# DM1098OAKW_USB.net
KiCad netlist of a schematic drawn in Altium Designer
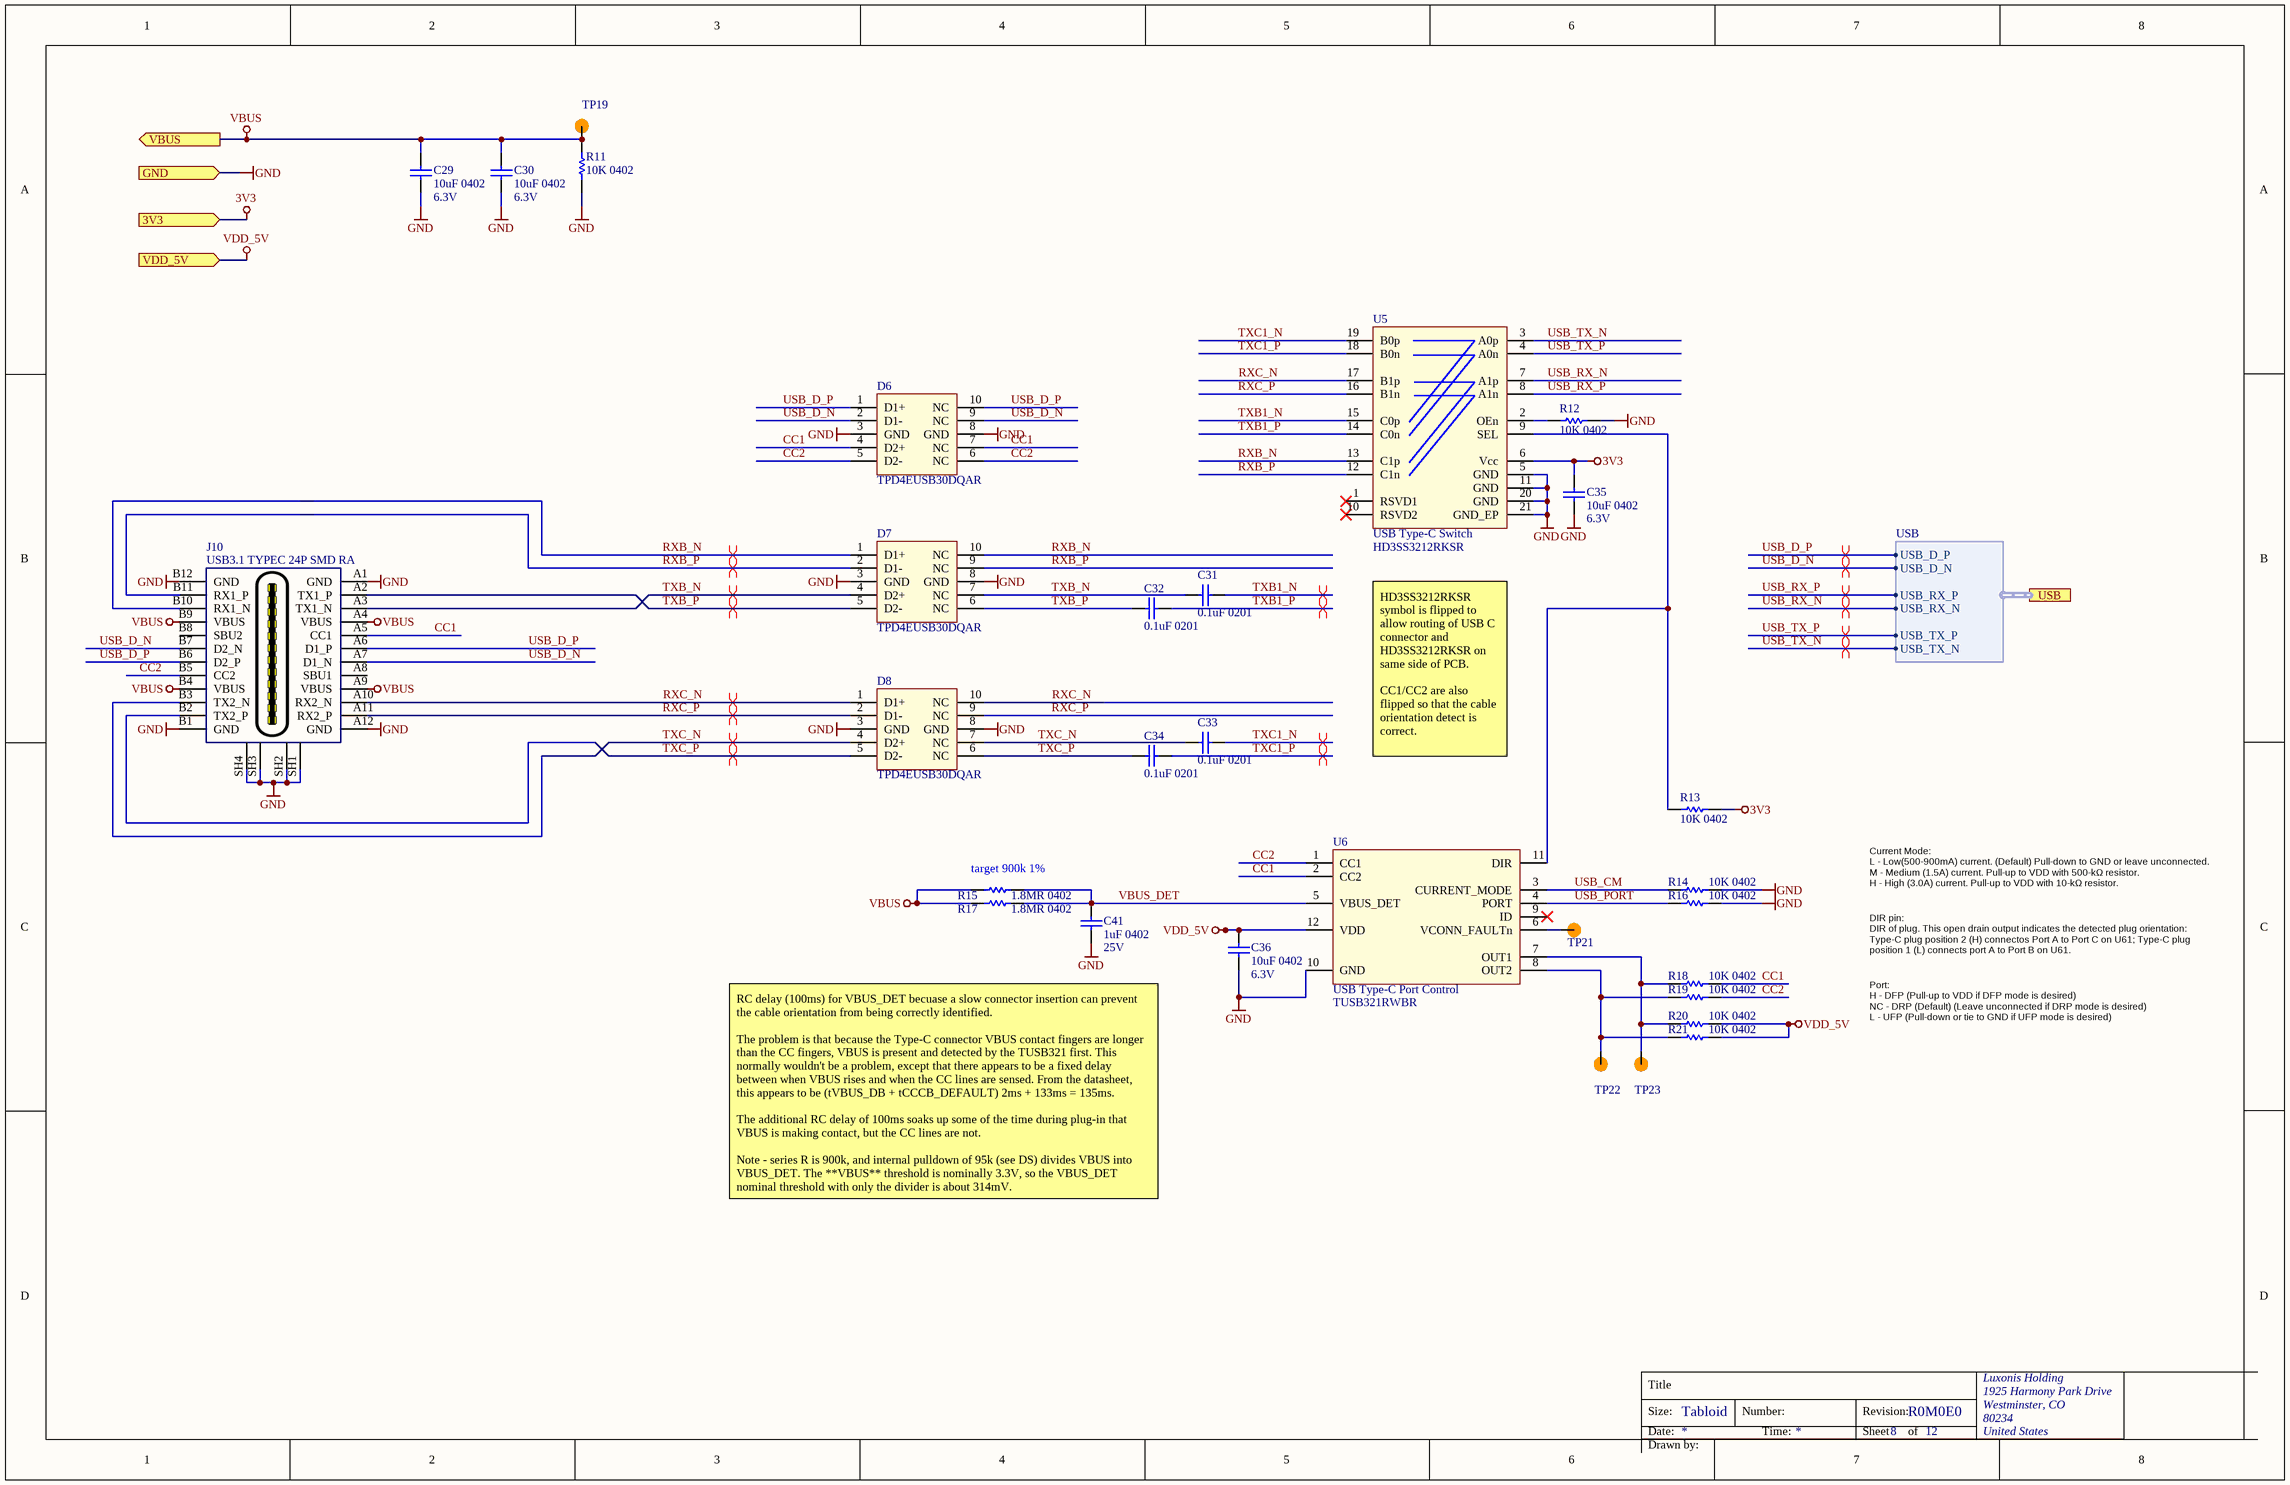
[diagram p0: DM1098OAKW_USB.SchDoc]

(export (version "E")
  (design (tool "Eeschema 10.0.6"))
  (components
    (comp (ref "C29")
      (value "10uF 0402")
      (footprint "CAP_Altium_Vault_Generic:CAPC0402(1005)70_L")
      (description "CAP CER 10UF 6.3V X5R 0402 20%")
      (fields (field (name "TOLERANCE") "20%") (field (name "VOLTAGE RATING") "6.3V"))
      (libsource (lib "LuxonisMaster") (part "GRM155R60J106ME15D"))
    )
    (comp (ref "C30")
      (value "10uF 0402")
      (footprint "CAP_Altium_Vault_Generic:CAPC0402(1005)70_L")
      (description "CAP CER 10UF 6.3V X5R 0402 20%")
      (fields (field (name "TOLERANCE") "20%") (field (name "VOLTAGE RATING") "6.3V"))
      (libsource (lib "LuxonisMaster") (part "GRM155R60J106ME15D"))
    )
    (comp (ref "C31")
      (value "0.1uF 0201")
      (footprint "CAP_Altium_Vault_Generic:CAPC0201(0603)33_L")
      (description "CAP CER 0.1UF 10V X5R 0201")
      (fields (field (name "TOLERANCE") "10%") (field (name "VOLTAGE") "10V"))
      (libsource (lib "LuxonisMaster") (part "GRM033R61A104KE15D"))
    )
    (comp (ref "C32")
      (value "0.1uF 0201")
      (footprint "CAP_Altium_Vault_Generic:CAPC0201(0603)33_L")
      (description "CAP CER 0.1UF 10V X5R 0201")
      (fields (field (name "TOLERANCE") "10%") (field (name "VOLTAGE") "10V"))
      (libsource (lib "LuxonisMaster") (part "GRM033R61A104KE15D"))
    )
    (comp (ref "C33")
      (value "0.1uF 0201")
      (footprint "CAP_Altium_Vault_Generic:CAPC0201(0603)33_L")
      (description "CAP CER 0.1UF 10V X5R 0201")
      (fields (field (name "TOLERANCE") "10%") (field (name "VOLTAGE") "10V"))
      (libsource (lib "LuxonisMaster") (part "GRM033R61A104KE15D"))
    )
    (comp (ref "C34")
      (value "0.1uF 0201")
      (footprint "CAP_Altium_Vault_Generic:CAPC0201(0603)33_L")
      (description "CAP CER 0.1UF 10V X5R 0201")
      (fields (field (name "TOLERANCE") "10%") (field (name "VOLTAGE") "10V"))
      (libsource (lib "LuxonisMaster") (part "GRM033R61A104KE15D"))
    )
    (comp (ref "C35")
      (value "10uF 0402")
      (footprint "CAP_Altium_Vault_Generic:CAPC0402(1005)70_L")
      (description "CAP CER 10UF 6.3V X5R 0402 20%")
      (fields (field (name "TOLERANCE") "20%") (field (name "VOLTAGE RATING") "6.3V"))
      (libsource (lib "LuxonisMaster") (part "GRM155R60J106ME15D"))
    )
    (comp (ref "C36")
      (value "10uF 0402")
      (footprint "CAP_Altium_Vault_Generic:CAPC0402(1005)70_L")
      (description "CAP CER 10UF 6.3V X5R 0402 20%")
      (fields (field (name "TOLERANCE") "20%") (field (name "VOLTAGE RATING") "6.3V"))
      (libsource (lib "LuxonisMaster") (part "GRM155R60J106ME15D"))
    )
    (comp (ref "C41")
      (value "1uF 0402")
      (footprint "CAP_Altium_Vault_Generic:CAPC0402(1005)70_N")
      (description "CAP CER 1UF 25V X5R 0402 10%")
      (fields
        (field (name "TOLERANCE") "10%")
        (field (name "VOLTAGE") "25V")
        (field (name "VOLTAGE RATING") "25V")
      )
      (libsource (lib "LuxonisMaster") (part "GRM155R61E105KA12D"))
    )
    (comp (ref "D6")
      (value "TPD4EUSB30DQAR")
      (footprint "LuxonisMaster:TPD4EUSB30DQAR")
      (description "TVS DIODE 5.5V 8V 10SON 8V Clamp 1A (8/20µs) Ipp Tvs Diode Surface Mount 10-USON (2.5x1)")
      (libsource (lib "LuxonisMaster") (part "TPD4EUSB30DQAR"))
    )
    (comp (ref "D7")
      (value "TPD4EUSB30DQAR")
      (footprint "LuxonisMaster:TPD4EUSB30DQAR")
      (description "TVS DIODE 5.5V 8V 10SON 8V Clamp 1A (8/20µs) Ipp Tvs Diode Surface Mount 10-USON (2.5x1)")
      (libsource (lib "LuxonisMaster") (part "TPD4EUSB30DQAR"))
    )
    (comp (ref "D8")
      (value "TPD4EUSB30DQAR")
      (footprint "LuxonisMaster:TPD4EUSB30DQAR")
      (description "TVS DIODE 5.5V 8V 10SON 8V Clamp 1A (8/20µs) Ipp Tvs Diode Surface Mount 10-USON (2.5x1)")
      (libsource (lib "LuxonisMaster") (part "TPD4EUSB30DQAR"))
    )
    (comp (ref "J10")
      (value "USB3.1 TYPEC 24P SMD RA")
      (footprint "LuxonisMaster:105450-0101")
      (description "CONN RCP USB3.1 TYPEC 24P SMD RA")
      (libsource (lib "LuxonisMaster") (part "105450-0101"))
    )
    (comp (ref "R11")
      (value "10K 0402")
      (footprint "RES_Altium_Vault_Generic:RESC0402(1005)_L")
      (fields (field (name "TOLERANCE") "1%"))
      (libsource (lib "LuxonisMaster") (part "RC0402FR-1310KL"))
    )
    (comp (ref "R12")
      (value "10K 0402")
      (footprint "RES_Altium_Vault_Generic:RESC0402(1005)_L")
      (fields (field (name "TOLERANCE") "1%"))
      (libsource (lib "LuxonisMaster") (part "RC0402FR-1310KL"))
    )
    (comp (ref "R13")
      (value "10K 0402")
      (footprint "RES_Altium_Vault_Generic:RESC0402(1005)_L")
      (fields (field (name "TOLERANCE") "1%"))
      (libsource (lib "LuxonisMaster") (part "RC0402FR-1310KL"))
    )
    (comp (ref "R14")
      (value "10K 0402")
      (footprint "RES_Altium_Vault_Generic:RESC0402(1005)_L")
      (fields (field (name "TOLERANCE") "1%"))
      (libsource (lib "LuxonisMaster") (part "RC0402FR-1310KL"))
    )
    (comp (ref "R15")
      (value "1.8MR 0402")
      (footprint "RES_Altium_Vault_Generic:RESC0402(1005)_L")
      (description "RES SMD 1.8M OHM 1% 1/16W 0402")
      (fields (field (name "TOLERANCE") "1%"))
      (libsource (lib "LuxonisMaster") (part "CRCW04021M80FKED"))
    )
    (comp (ref "R16")
      (value "10K 0402")
      (footprint "RES_Altium_Vault_Generic:RESC0402(1005)_L")
      (fields (field (name "TOLERANCE") "1%"))
      (libsource (lib "LuxonisMaster") (part "RC0402FR-1310KL"))
    )
    (comp (ref "R17")
      (value "1.8MR 0402")
      (footprint "RES_Altium_Vault_Generic:RESC0402(1005)_L")
      (description "RES SMD 1.8M OHM 1% 1/16W 0402")
      (fields (field (name "TOLERANCE") "1%"))
      (libsource (lib "LuxonisMaster") (part "CRCW04021M80FKED"))
    )
    (comp (ref "R18")
      (value "10K 0402")
      (footprint "RES_Altium_Vault_Generic:RESC0402(1005)_L")
      (fields (field (name "TOLERANCE") "1%"))
      (libsource (lib "LuxonisMaster") (part "RC0402FR-1310KL"))
    )
    (comp (ref "R19")
      (value "10K 0402")
      (footprint "RES_Altium_Vault_Generic:RESC0402(1005)_L")
      (fields (field (name "TOLERANCE") "1%"))
      (libsource (lib "LuxonisMaster") (part "RC0402FR-1310KL"))
    )
    (comp (ref "R20")
      (value "10K 0402")
      (footprint "RES_Altium_Vault_Generic:RESC0402(1005)_L")
      (fields (field (name "TOLERANCE") "1%"))
      (libsource (lib "LuxonisMaster") (part "RC0402FR-1310KL"))
    )
    (comp (ref "R21")
      (value "10K 0402")
      (footprint "RES_Altium_Vault_Generic:RESC0402(1005)_L")
      (fields (field (name "TOLERANCE") "1%"))
      (libsource (lib "LuxonisMaster") (part "RC0402FR-1310KL"))
    )
    (comp (ref "TP19")
      (value "TP100_200_NS")
      (footprint "LuxonisMaster:TP100_200_NS")
      (libsource (lib "LuxonisMaster") (part "TEST_POINT"))
    )
    (comp (ref "TP21")
      (value "TP075_150_NS")
      (footprint "LuxonisMaster:TP075_150_NS")
      (libsource (lib "LuxonisMaster") (part "TEST_POINT"))
    )
    (comp (ref "TP22")
      (value "TP075_150_NS")
      (footprint "LuxonisMaster:TP075_150_NS")
      (libsource (lib "LuxonisMaster") (part "TEST_POINT"))
    )
    (comp (ref "TP23")
      (value "TP075_150_NS")
      (footprint "LuxonisMaster:TP075_150_NS")
      (libsource (lib "LuxonisMaster") (part "TEST_POINT"))
    )
    (comp (ref "U5")
      (value "USB Type-C Switch")
      (footprint "LuxonisMaster:HD3SS3212RKSR")
      (description "IC MUX 2:1 8 OHM 20VQFN")
      (fields (field (name "MANUFACTURER PART NUMBER 1") "HD3SS3212RKSR"))
      (libsource (lib "LuxonisMaster") (part "HD3SS3212RKSR"))
    )
    (comp (ref "U6")
      (value "USB Type-C Port Control")
      (footprint "LuxonisMaster:TUSB321RWBR")
      (description "IC USB PORT CONTROL TYPE-C 12X2Q")
      (fields (field (name "MANUFACTURER PART NUMBER 1") "TUSB321RWBR"))
      (libsource (lib "LuxonisMaster") (part "TUSB321RWBR"))
    )
  )
  (nets
    (net (code "2") (name "/CC1") (class "Default")
      (node (ref "D6") (pin "4") (pinfunction "D2+_4") (pintype "passive"))
      (node (ref "D6") (pin "7") (pinfunction "NC_7") (pintype "passive"))
      (node (ref "J10") (pin "A5") (pinfunction "CC1_A5") (pintype "passive"))
      (node (ref "R18") (pin "2") (pinfunction "2_2") (pintype "passive"))
      (node (ref "U6") (pin "2") (pinfunction "CC2_2") (pintype "passive"))
    )
    (net (code "3") (name "/CC2") (class "Default")
      (node (ref "D6") (pin "5") (pinfunction "D2-_5") (pintype "passive"))
      (node (ref "D6") (pin "6") (pinfunction "NC_6") (pintype "passive"))
      (node (ref "J10") (pin "B5") (pinfunction "CC2_B5") (pintype "passive"))
      (node (ref "R19") (pin "2") (pinfunction "2_2") (pintype "passive"))
      (node (ref "U6") (pin "1") (pinfunction "CC1_1") (pintype "passive"))
    )
    (net (code "4") (name "/RXB_N") (class "Default")
      (node (ref "D7") (pin "1") (pinfunction "D1+_1") (pintype "passive"))
      (node (ref "D7") (pin "10") (pinfunction "NC_10") (pintype "passive"))
      (node (ref "J10") (pin "B10") (pinfunction "RX1_N_B10") (pintype "passive"))
      (node (ref "U5") (pin "13") (pinfunction "C1p_13") (pintype "passive"))
    )
    (net (code "5") (name "/RXB_P") (class "Default")
      (node (ref "D7") (pin "2") (pinfunction "D1-_2") (pintype "passive"))
      (node (ref "D7") (pin "9") (pinfunction "NC_9") (pintype "passive"))
      (node (ref "J10") (pin "B11") (pinfunction "RX1_P_B11") (pintype "passive"))
      (node (ref "U5") (pin "12") (pinfunction "C1n_12") (pintype "passive"))
    )
    (net (code "6") (name "/RXC_N") (class "Default")
      (node (ref "D8") (pin "1") (pinfunction "D1+_1") (pintype "passive"))
      (node (ref "D8") (pin "10") (pinfunction "NC_10") (pintype "passive"))
      (node (ref "J10") (pin "A10") (pinfunction "RX2_N_A10") (pintype "passive"))
      (node (ref "U5") (pin "17") (pinfunction "B1p_17") (pintype "passive"))
    )
    (net (code "7") (name "/RXC_P") (class "Default")
      (node (ref "D8") (pin "2") (pinfunction "D1-_2") (pintype "passive"))
      (node (ref "D8") (pin "9") (pinfunction "NC_9") (pintype "passive"))
      (node (ref "J10") (pin "A11") (pinfunction "RX2_P_A11") (pintype "passive"))
      (node (ref "U5") (pin "16") (pinfunction "B1n_16") (pintype "passive"))
    )
    (net (code "8") (name "/TXB1_N") (class "Default")
      (node (ref "C31") (pin "2") (pinfunction "2_2") (pintype "passive"))
      (node (ref "U5") (pin "15") (pinfunction "C0p_15") (pintype "passive"))
    )
    (net (code "9") (name "/TXB1_P") (class "Default")
      (node (ref "C32") (pin "2") (pinfunction "2_2") (pintype "passive"))
      (node (ref "U5") (pin "14") (pinfunction "C0n_14") (pintype "passive"))
    )
    (net (code "10") (name "/TXB_N") (class "Default")
      (node (ref "C31") (pin "1") (pinfunction "1_1") (pintype "passive"))
      (node (ref "D7") (pin "4") (pinfunction "D2+_4") (pintype "passive"))
      (node (ref "D7") (pin "7") (pinfunction "NC_7") (pintype "passive"))
      (node (ref "J10") (pin "A3") (pinfunction "TX1_N_A3") (pintype "passive"))
    )
    (net (code "11") (name "/TXB_P") (class "Default")
      (node (ref "C32") (pin "1") (pinfunction "1_1") (pintype "passive"))
      (node (ref "D7") (pin "5") (pinfunction "D2-_5") (pintype "passive"))
      (node (ref "D7") (pin "6") (pinfunction "NC_6") (pintype "passive"))
      (node (ref "J10") (pin "A2") (pinfunction "TX1_P_A2") (pintype "passive"))
    )
    (net (code "12") (name "/TXC1_N") (class "Default")
      (node (ref "C33") (pin "2") (pinfunction "2_2") (pintype "passive"))
      (node (ref "U5") (pin "19") (pinfunction "B0p_19") (pintype "passive"))
    )
    (net (code "13") (name "/TXC1_P") (class "Default")
      (node (ref "C34") (pin "2") (pinfunction "2_2") (pintype "passive"))
      (node (ref "U5") (pin "18") (pinfunction "B0n_18") (pintype "passive"))
    )
    (net (code "14") (name "/TXC_N") (class "Default")
      (node (ref "C33") (pin "1") (pinfunction "1_1") (pintype "passive"))
      (node (ref "D8") (pin "4") (pinfunction "D2+_4") (pintype "passive"))
      (node (ref "D8") (pin "7") (pinfunction "NC_7") (pintype "passive"))
      (node (ref "J10") (pin "B3") (pinfunction "TX2_N_B3") (pintype "passive"))
    )
    (net (code "15") (name "/TXC_P") (class "Default")
      (node (ref "C34") (pin "1") (pinfunction "1_1") (pintype "passive"))
      (node (ref "D8") (pin "5") (pinfunction "D2-_5") (pintype "passive"))
      (node (ref "D8") (pin "6") (pinfunction "NC_6") (pintype "passive"))
      (node (ref "J10") (pin "B2") (pinfunction "TX2_P_B2") (pintype "passive"))
    )
    (net (code "16") (name "/USB_CM") (class "Default")
      (node (ref "R14") (pin "1") (pinfunction "1_1") (pintype "passive"))
      (node (ref "U6") (pin "3") (pinfunction "CURRENT_MODE_3") (pintype "passive"))
    )
    (net (code "17") (name "/USB_D_N") (class "Default")
      (node (ref "D6") (pin "2") (pinfunction "D1-_2") (pintype "passive"))
      (node (ref "D6") (pin "9") (pinfunction "NC_9") (pintype "passive"))
      (node (ref "J10") (pin "A7") (pinfunction "D1_N_A7") (pintype "passive"))
      (node (ref "J10") (pin "B7") (pinfunction "D2_N_B7") (pintype "passive"))
    )
    (net (code "18") (name "/USB_D_P") (class "Default")
      (node (ref "D6") (pin "1") (pinfunction "D1+_1") (pintype "passive"))
      (node (ref "D6") (pin "10") (pinfunction "NC_10") (pintype "passive"))
      (node (ref "J10") (pin "A6") (pinfunction "D1_P_A6") (pintype "passive"))
      (node (ref "J10") (pin "B6") (pinfunction "D2_P_B6") (pintype "passive"))
    )
    (net (code "19") (name "/USB_PORT") (class "Default")
      (node (ref "R16") (pin "1") (pinfunction "1_1") (pintype "passive"))
      (node (ref "U6") (pin "4") (pinfunction "PORT_4") (pintype "passive"))
    )
    (net (code "20") (name "/USB_RX_N") (class "Default")
      (node (ref "U5") (pin "7") (pinfunction "A1p_7") (pintype "passive"))
    )
    (net (code "21") (name "/USB_RX_P") (class "Default")
      (node (ref "U5") (pin "8") (pinfunction "A1n_8") (pintype "passive"))
    )
    (net (code "22") (name "/USB_TX_N") (class "Default")
      (node (ref "U5") (pin "3") (pinfunction "A0p_3") (pintype "passive"))
    )
    (net (code "23") (name "/USB_TX_P") (class "Default")
      (node (ref "U5") (pin "4") (pinfunction "A0n_4") (pintype "passive"))
    )
    (net (code "24") (name "/VBUS_DET") (class "Default")
      (node (ref "C41") (pin "2") (pinfunction "2_2") (pintype "passive"))
      (node (ref "R15") (pin "2") (pinfunction "2_2") (pintype "passive"))
      (node (ref "R17") (pin "2") (pinfunction "2_2") (pintype "passive"))
      (node (ref "U6") (pin "5") (pinfunction "VBUS_DET_5") (pintype "passive"))
    )
    (net (code "26") (name "3V3") (class "Default")
      (node (ref "C35") (pin "2") (pinfunction "2_2") (pintype "passive"))
      (node (ref "R13") (pin "2") (pinfunction "2_2") (pintype "passive"))
      (node (ref "U5") (pin "6") (pinfunction "Vcc_6") (pintype "passive"))
    )
    (net (code "27") (name "GND") (class "Default")
      (node (ref "C29") (pin "1") (pinfunction "1_1") (pintype "passive"))
      (node (ref "C30") (pin "1") (pinfunction "1_1") (pintype "passive"))
      (node (ref "C35") (pin "1") (pinfunction "1_1") (pintype "passive"))
      (node (ref "C36") (pin "1") (pinfunction "1_1") (pintype "passive"))
      (node (ref "C41") (pin "1") (pinfunction "1_1") (pintype "passive"))
      (node (ref "D6") (pin "3") (pinfunction "GND_3") (pintype "passive"))
      (node (ref "D6") (pin "8") (pinfunction "GND_8") (pintype "passive"))
      (node (ref "D7") (pin "3") (pinfunction "GND_3") (pintype "passive"))
      (node (ref "D7") (pin "8") (pinfunction "GND_8") (pintype "passive"))
      (node (ref "D8") (pin "3") (pinfunction "GND_3") (pintype "passive"))
      (node (ref "D8") (pin "8") (pinfunction "GND_8") (pintype "passive"))
      (node (ref "J10") (pin "A1") (pinfunction "GND_A1") (pintype "passive"))
      (node (ref "J10") (pin "A12") (pinfunction "GND_A12") (pintype "passive"))
      (node (ref "J10") (pin "B1") (pinfunction "GND_B1") (pintype "passive"))
      (node (ref "J10") (pin "B12") (pinfunction "GND_B12") (pintype "passive"))
      (node (ref "J10") (pin "SH1") (pinfunction "SH_SH1") (pintype "passive"))
      (node (ref "J10") (pin "SH2") (pinfunction "SH_SH2") (pintype "passive"))
      (node (ref "J10") (pin "SH3") (pinfunction "SH_SH3") (pintype "passive"))
      (node (ref "J10") (pin "SH4") (pinfunction "SH_SH4") (pintype "passive"))
      (node (ref "R11") (pin "1") (pinfunction "1_1") (pintype "passive"))
      (node (ref "R12") (pin "2") (pinfunction "2_2") (pintype "passive"))
      (node (ref "R14") (pin "2") (pinfunction "2_2") (pintype "passive"))
      (node (ref "R16") (pin "2") (pinfunction "2_2") (pintype "passive"))
      (node (ref "U5") (pin "11") (pinfunction "GND_11") (pintype "passive"))
      (node (ref "U5") (pin "20") (pinfunction "GND_20") (pintype "passive"))
      (node (ref "U5") (pin "21") (pinfunction "GND_EP_21") (pintype "passive"))
      (node (ref "U5") (pin "5") (pinfunction "GND_5") (pintype "passive"))
      (node (ref "U6") (pin "10") (pinfunction "GND_10") (pintype "passive"))
    )
    (net (code "28") (name "Net-(U5-OEn)") (class "Default")
      (node (ref "R12") (pin "1") (pinfunction "1_1") (pintype "passive"))
      (node (ref "U5") (pin "2") (pinfunction "OEn_2") (pintype "passive"))
    )
    (net (code "29") (name "Net-(U5-SEL)") (class "Default")
      (node (ref "R13") (pin "1") (pinfunction "1_1") (pintype "passive"))
      (node (ref "U5") (pin "9") (pinfunction "SEL_9") (pintype "passive"))
      (node (ref "U6") (pin "11") (pinfunction "DIR_11") (pintype "passive"))
    )
    (net (code "30") (name "Net-(U6-OUT1)") (class "Default")
      (node (ref "R18") (pin "1") (pinfunction "1_1") (pintype "passive"))
      (node (ref "R20") (pin "1") (pinfunction "1_1") (pintype "passive"))
      (node (ref "TP23") (pin "1") (pintype "passive"))
      (node (ref "U6") (pin "7") (pinfunction "OUT1_7") (pintype "passive"))
    )
    (net (code "31") (name "Net-(U6-OUT2)") (class "Default")
      (node (ref "R19") (pin "1") (pinfunction "1_1") (pintype "passive"))
      (node (ref "R21") (pin "1") (pinfunction "1_1") (pintype "passive"))
      (node (ref "TP22") (pin "1") (pintype "passive"))
      (node (ref "U6") (pin "8") (pinfunction "OUT2_8") (pintype "passive"))
    )
    (net (code "32") (name "Net-(U6-VCONN_FAULTn)") (class "Default")
      (node (ref "TP21") (pin "1") (pintype "passive"))
      (node (ref "U6") (pin "6") (pinfunction "VCONN_FAULTn_6") (pintype "passive"))
    )
    (net (code "33") (name "VBUS") (class "Default")
      (node (ref "C29") (pin "2") (pinfunction "2_2") (pintype "passive"))
      (node (ref "C30") (pin "2") (pinfunction "2_2") (pintype "passive"))
      (node (ref "J10") (pin "A4") (pinfunction "VBUS_A4") (pintype "passive"))
      (node (ref "J10") (pin "A9") (pinfunction "VBUS_A9") (pintype "passive"))
      (node (ref "J10") (pin "B4") (pinfunction "VBUS_B4") (pintype "passive"))
      (node (ref "J10") (pin "B9") (pinfunction "VBUS_B9") (pintype "passive"))
      (node (ref "R11") (pin "2") (pinfunction "2_2") (pintype "passive"))
      (node (ref "R15") (pin "1") (pinfunction "1_1") (pintype "passive"))
      (node (ref "R17") (pin "1") (pinfunction "1_1") (pintype "passive"))
      (node (ref "TP19") (pin "1") (pintype "passive"))
    )
    (net (code "34") (name "VDD_5V") (class "Default")
      (node (ref "C36") (pin "2") (pinfunction "2_2") (pintype "passive"))
      (node (ref "R20") (pin "2") (pinfunction "2_2") (pintype "passive"))
      (node (ref "R21") (pin "2") (pinfunction "2_2") (pintype "passive"))
      (node (ref "U6") (pin "12") (pinfunction "VDD_12") (pintype "passive"))
    )
    (net (code "35") (name "unconnected-(J10-SBU1-PadA8)") (class "Default")
      (node (ref "J10") (pin "A8") (pinfunction "SBU1_A8") (pintype "passive"))
    )
    (net (code "36") (name "unconnected-(J10-SBU2-PadB8)") (class "Default")
      (node (ref "J10") (pin "B8") (pinfunction "SBU2_B8") (pintype "passive"))
    )
    (net (code "37") (name "unconnected-(U5-RSVD1-Pad1)") (class "Default")
      (node (ref "U5") (pin "1") (pinfunction "RSVD1_1") (pintype "passive+no_connect"))
    )
    (net (code "38") (name "unconnected-(U5-RSVD2-Pad10)") (class "Default")
      (node (ref "U5") (pin "10") (pinfunction "RSVD2_10") (pintype "passive+no_connect"))
    )
    (net (code "39") (name "unconnected-(U6-ID-Pad9)") (class "Default")
      (node (ref "U6") (pin "9") (pinfunction "ID_9") (pintype "passive+no_connect"))
    )
  )
)
